# SCH_Tanbre_v2_2026-05-30_4.net
KiCad netlist of a schematic drawn in EasyEDA
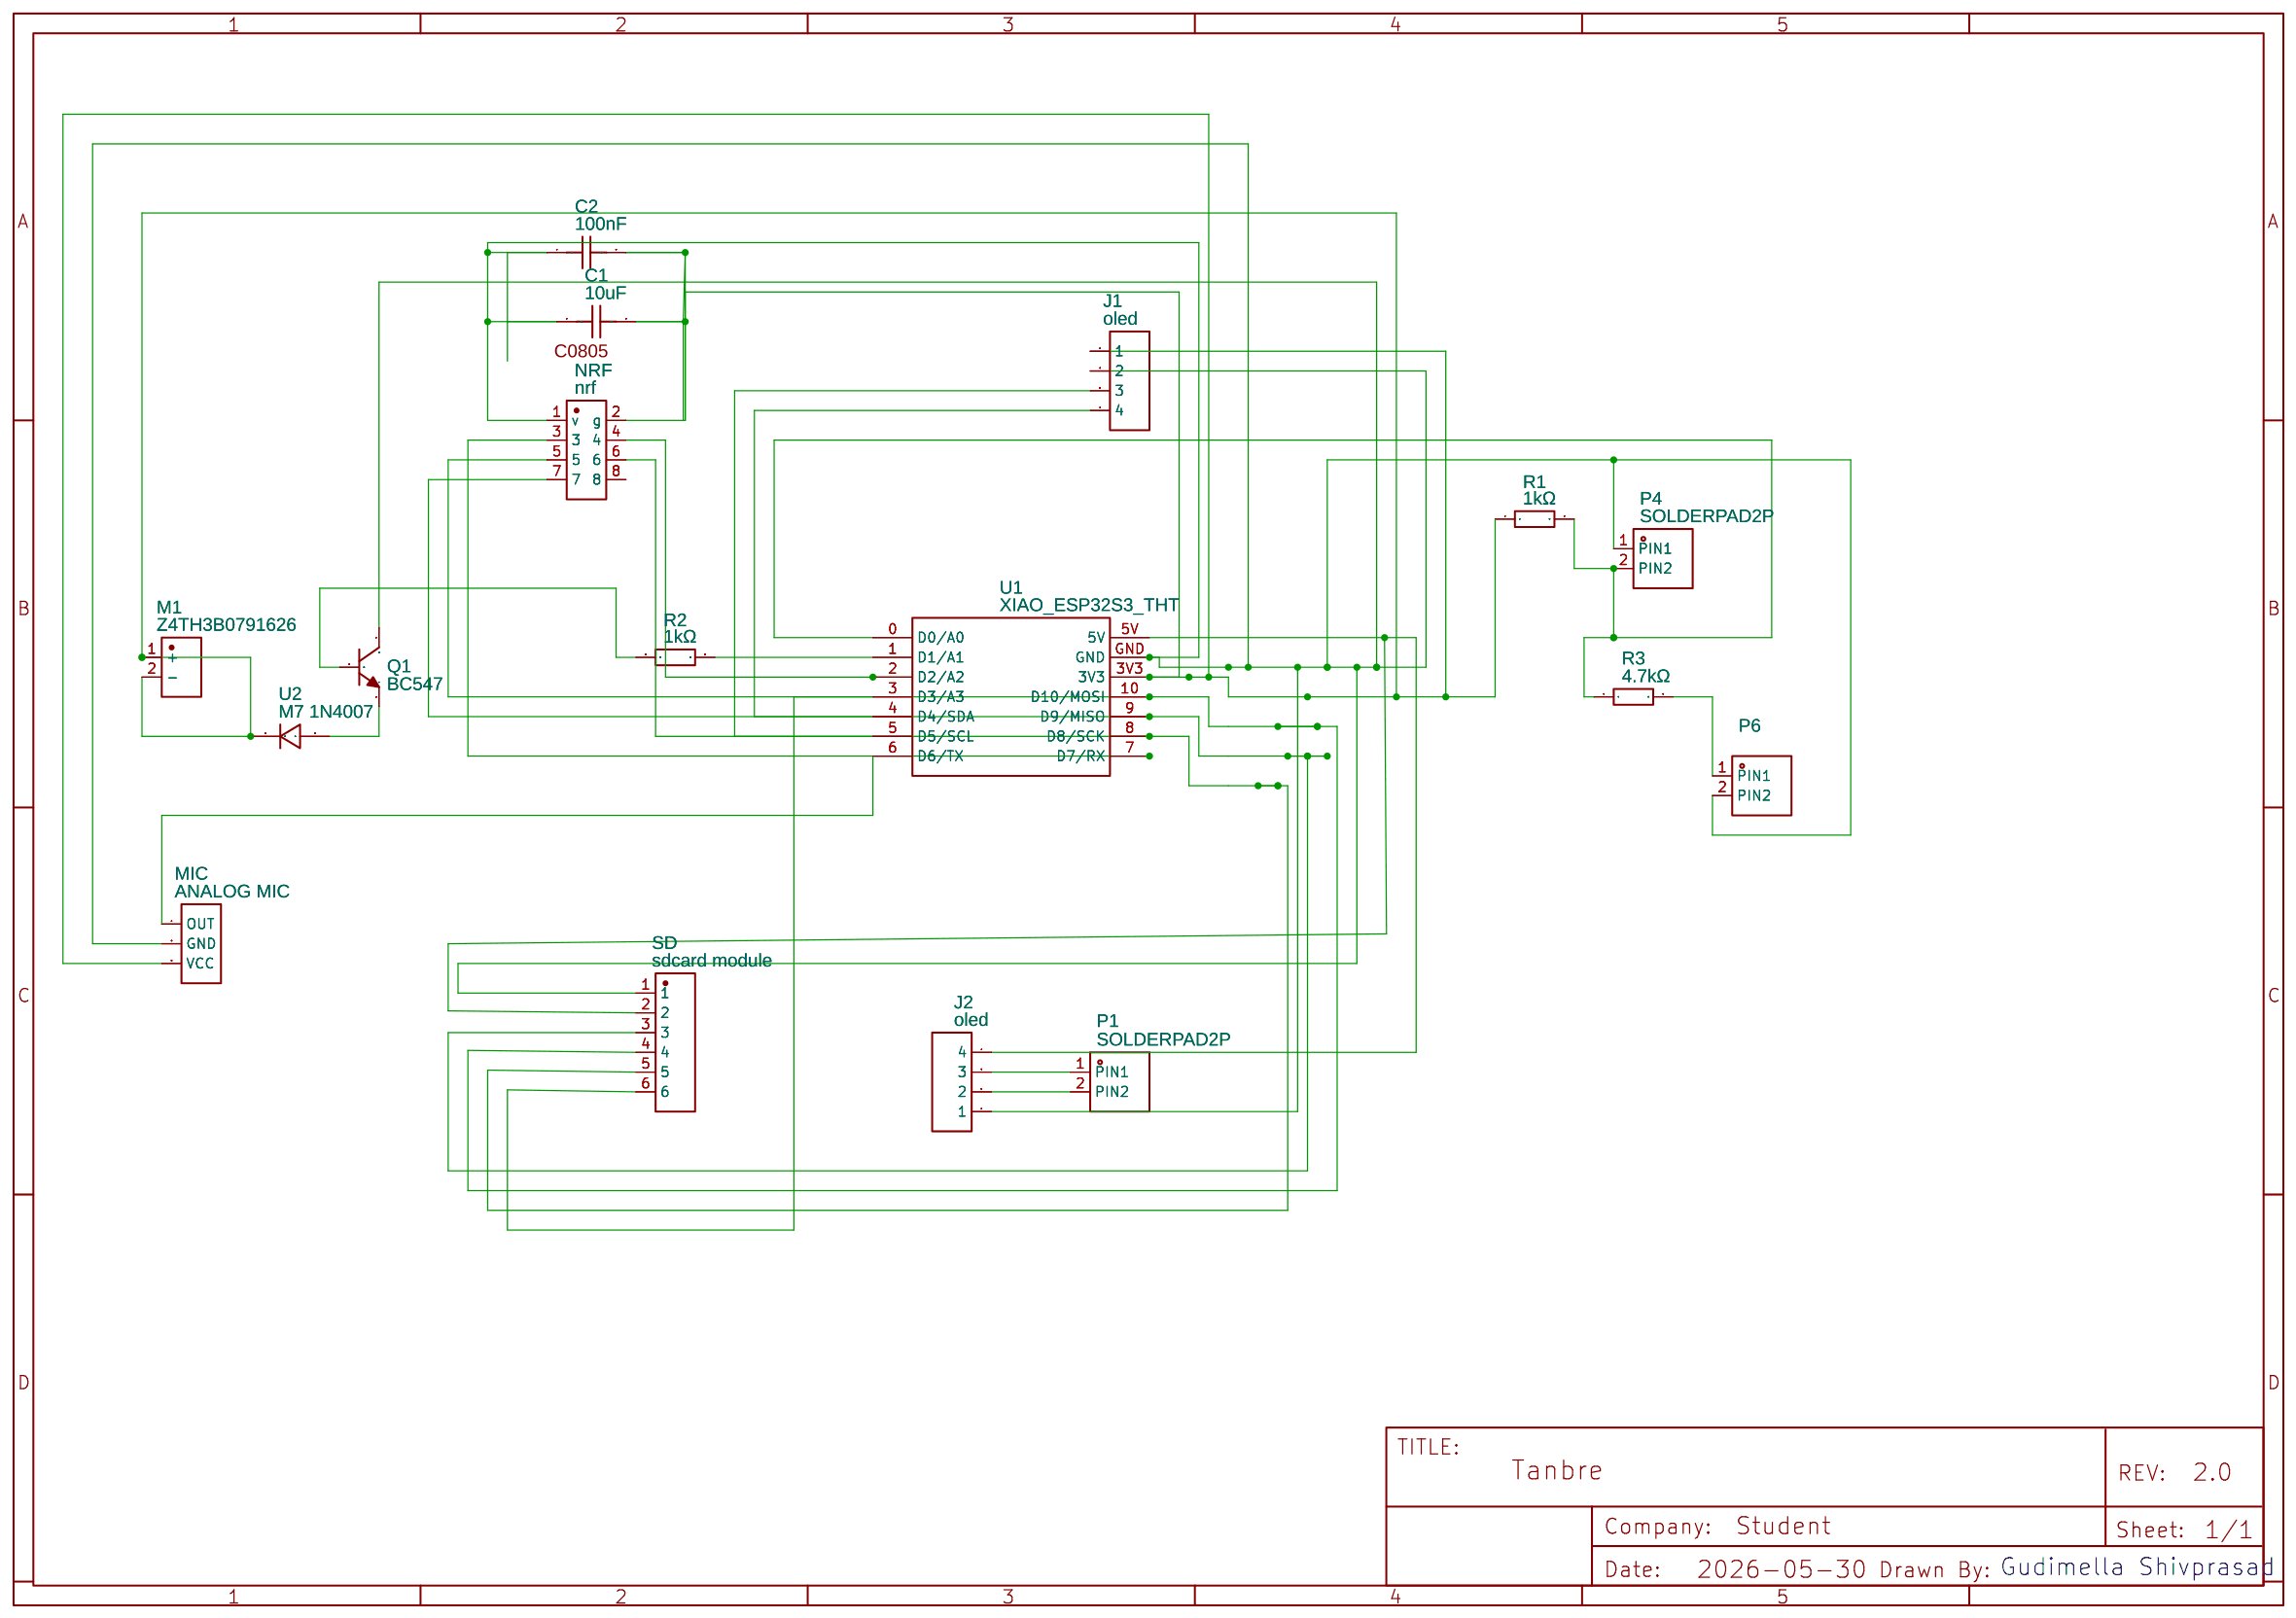
[diagram p0: schematic sheet]

(export (version "E")
  (design (tool "Eeschema 10.0.6"))
  (components
    (comp (ref "C1")
      (value "10uF")
      (fields
        (field (name "Manufacturer Part") "V106K0805X5R250NHP")
        (field (name "Manufacturer") "VIIYONG(微容)")
      )
      (libsource (lib "") (part "V106K0805X5R250NHP"))
    )
    (comp (ref "C2")
      (value "100nF")
      (fields
        (field (name "Manufacturer Part") "VJ0805Y104KXXCW1BC")
        (field (name "Manufacturer") "VISHAY(威世)")
      )
      (libsource (lib "") (part "VJ0805Y104KXXCW1BC"))
    )
    (comp (ref "J1") (value "oled") (libsource (lib "") (part "HDR-M-2.54_1x4_1")))
    (comp (ref "J2") (value "oled") (libsource (lib "") (part "HDR-M-2.54_1x4")))
    (comp (ref "M1")
      (value "Z4TH3B0791626")
      (fields (field (name "Manufacturer") "KOTL(金龙机电)"))
      (libsource (lib "") (part "Z4TH3B0791626"))
    )
    (comp (ref "MIC") (value "ANALOG MIC") (libsource (lib "") (part "HDR-M-2.54_1x3")))
    (comp (ref "NRF")
      (value "nrf")
      (fields (field (name "Manufacturer Part") "2X4 DIP"))
      (libsource (lib "") (part "2X4 DIP"))
    )
    (comp (ref "P1")
      (value "SOLDERPAD2P")
      (fields (field (name "Manufacturer Part") "New SchematicLib"))
      (libsource (lib "") (part "SOLDERPAD2P"))
    )
    (comp (ref "P4")
      (value "SOLDERPAD2P")
      (fields (field (name "Manufacturer Part") "New SchematicLib"))
      (libsource (lib "") (part "SOLDERPAD2P"))
    )
    (comp (ref "P6")
      (value "SOLDERPAD2P")
      (fields (field (name "Manufacturer Part") "New SchematicLib"))
      (libsource (lib "") (part "SOLDERPAD2P"))
    )
    (comp (ref "Q1")
      (value "BC547")
      (fields
        (field (name "Manufacturer Part") "BC547(RANGE:420-800)")
        (field (name "Manufacturer") "CJ(江苏长电/长晶)")
      )
      (libsource (lib "") (part "BC547"))
    )
    (comp (ref "R1")
      (value "1kΩ")
      (fields (field (name "Manufacturer Part") "CR-02JL6----1K") (field (name "Manufacturer") "Viking(光颉)"))
      (libsource (lib "") (part "CR-02JL6----1K"))
    )
    (comp (ref "R2")
      (value "1kΩ")
      (fields (field (name "Manufacturer Part") "CR-02JL6----1K") (field (name "Manufacturer") "Viking(光颉)"))
      (libsource (lib "") (part "CR-02JL6----1K"))
    )
    (comp (ref "R3")
      (value "4.7kΩ")
      (fields (field (name "Manufacturer Part") "RMC12064.7K5%N") (field (name "Manufacturer") "Tyohm(幸亚电阻)"))
      (libsource (lib "") (part "RMC12064.7K5%N"))
    )
    (comp (ref "SD")
      (value "sdcard module")
      (fields
        (field (name "Manufacturer Part") "HC-PM254-5.0H-1x6PZ")
        (field (name "Manufacturer") "HC(虹成电子)")
      )
      (libsource (lib "") (part "HC-PM254-5.0H-1X6PZ"))
    )
    (comp (ref "U1") (value "XIAO_ESP32S3_THT") (libsource (lib "") (part "XIAO_ESP32S3_THT")))
    (comp (ref "U2")
      (value "M7 1N4007")
      (fields (field (name "Manufacturer") "JUXING(钜兴)"))
      (libsource (lib "") (part "M7 1N4007"))
    )
  )
  (nets
    (net (code "1") (name "Net-(J2-Pad4)") (class "Default")
      (node (ref "J2") (pin "4") (pinfunction "4_4") (pintype "unspecified"))
      (node (ref "SD") (pin "2") (pinfunction "2_2") (pintype "unspecified"))
      (node (ref "U1") (pin "5V") (pinfunction "5V_5V") (pintype "unspecified"))
    )
    (net (code "2") (name "Net-(M1-+)") (class "Default")
      (node (ref "C1") (pin "2") (pinfunction "2_2") (pintype "unspecified"))
      (node (ref "C2") (pin "2") (pinfunction "2_2") (pintype "unspecified"))
      (node (ref "J1") (pin "1") (pinfunction "1_1") (pintype "unspecified"))
      (node (ref "M1") (pin "1") (pinfunction "+_1") (pintype "unspecified"))
      (node (ref "M1") (pin "2") (pinfunction "-_2") (pintype "unspecified"))
      (node (ref "MIC") (pin "3") (pinfunction "VCC_3") (pintype "unspecified"))
      (node (ref "NRF") (pin "2") (pinfunction "g_2") (pintype "unspecified"))
      (node (ref "R1") (pin "1") (pinfunction "1_1") (pintype "unspecified"))
      (node (ref "U1") (pin "3V3") (pinfunction "3V3_3V3") (pintype "unspecified"))
      (node (ref "U2") (pin "1") (pinfunction "1_1") (pintype "unspecified"))
    )
    (net (code "3") (name "Net-(MIC-GND)") (class "Default")
      (node (ref "C1") (pin "1") (pinfunction "1_1") (pintype "unspecified"))
      (node (ref "C2") (pin "1") (pinfunction "1_1") (pintype "unspecified"))
      (node (ref "J1") (pin "2") (pinfunction "2_2") (pintype "unspecified"))
      (node (ref "J2") (pin "1") (pinfunction "1_1") (pintype "unspecified"))
      (node (ref "MIC") (pin "2") (pinfunction "GND_2") (pintype "unspecified"))
      (node (ref "NRF") (pin "1") (pinfunction "v_1") (pintype "unspecified"))
      (node (ref "P4") (pin "1") (pinfunction "PIN1_1") (pintype "unspecified"))
      (node (ref "P6") (pin "2") (pinfunction "PIN2_2") (pintype "unspecified"))
      (node (ref "Q1") (pin "1") (pinfunction "C_1") (pintype "unspecified"))
      (node (ref "SD") (pin "1") (pinfunction "1_1") (pintype "unspecified"))
      (node (ref "U1") (pin "GND") (pinfunction "GND_GND") (pintype "unspecified"))
    )
    (net (code "4") (name "Net-(MIC-OUT)") (class "Default")
      (node (ref "MIC") (pin "1") (pinfunction "OUT_1") (pintype "unspecified"))
      (node (ref "U1") (pin "6") (pinfunction "D6/TX_6") (pintype "unspecified"))
    )
    (net (code "5") (name "Net-(P1-PIN1)") (class "Default")
      (node (ref "J2") (pin "3") (pinfunction "3_3") (pintype "unspecified"))
      (node (ref "P1") (pin "1") (pinfunction "PIN1_1") (pintype "unspecified"))
    )
    (net (code "6") (name "Net-(P1-PIN2)") (class "Default")
      (node (ref "J2") (pin "2") (pinfunction "2_2") (pintype "unspecified"))
      (node (ref "P1") (pin "2") (pinfunction "PIN2_2") (pintype "unspecified"))
    )
    (net (code "7") (name "Net-(P4-PIN2)") (class "Default")
      (node (ref "P4") (pin "2") (pinfunction "PIN2_2") (pintype "unspecified"))
      (node (ref "R1") (pin "2") (pinfunction "2_2") (pintype "unspecified"))
      (node (ref "R3") (pin "1") (pinfunction "1_1") (pintype "unspecified"))
      (node (ref "U1") (pin "0") (pinfunction "D0/A0_0") (pintype "unspecified"))
    )
    (net (code "8") (name "Net-(P6-PIN1)") (class "Default")
      (node (ref "P6") (pin "1") (pinfunction "PIN1_1") (pintype "unspecified"))
      (node (ref "R3") (pin "2") (pinfunction "2_2") (pintype "unspecified"))
    )
    (net (code "9") (name "Net-(Q1-B)") (class "Default")
      (node (ref "Q1") (pin "2") (pinfunction "B_2") (pintype "unspecified"))
      (node (ref "R2") (pin "1") (pinfunction "1_1") (pintype "unspecified"))
    )
    (net (code "10") (name "Net-(Q1-E)") (class "Default")
      (node (ref "Q1") (pin "3") (pinfunction "E_3") (pintype "unspecified"))
      (node (ref "U2") (pin "2") (pinfunction "2_2") (pintype "unspecified"))
    )
    (net (code "11") (name "Net-(U1-D1{slash}A1)") (class "Default")
      (node (ref "R2") (pin "2") (pinfunction "2_2") (pintype "unspecified"))
      (node (ref "U1") (pin "1") (pinfunction "D1/A1_1") (pintype "unspecified"))
    )
    (net (code "12") (name "Net-(U1-D2{slash}A2)") (class "Default")
      (node (ref "NRF") (pin "4") (pinfunction "4_4") (pintype "unspecified"))
      (node (ref "U1") (pin "2") (pinfunction "D2/A2_2") (pintype "unspecified"))
    )
    (net (code "13") (name "Net-(U1-D3{slash}A3)") (class "Default")
      (node (ref "SD") (pin "6") (pinfunction "6_6") (pintype "unspecified"))
      (node (ref "U1") (pin "3") (pinfunction "D3/A3_3") (pintype "unspecified"))
    )
    (net (code "14") (name "Net-(U1-D4{slash}SDA)") (class "Default")
      (node (ref "J1") (pin "4") (pinfunction "4_4") (pintype "unspecified"))
      (node (ref "U1") (pin "4") (pinfunction "D4/SDA_4") (pintype "unspecified"))
    )
    (net (code "15") (name "Net-(U1-D5{slash}SCL)") (class "Default")
      (node (ref "J1") (pin "3") (pinfunction "3_3") (pintype "unspecified"))
      (node (ref "U1") (pin "5") (pinfunction "D5/SCL_5") (pintype "unspecified"))
    )
    (net (code "16") (name "Net-(U1-D7{slash}RX)") (class "Default")
      (node (ref "NRF") (pin "3") (pinfunction "3_3") (pintype "unspecified"))
      (node (ref "U1") (pin "7") (pinfunction "D7/RX_7") (pintype "unspecified"))
    )
    (net (code "17") (name "Net-(U1-D8{slash}SCK)") (class "Default")
      (node (ref "NRF") (pin "6") (pinfunction "6_6") (pintype "unspecified"))
      (node (ref "SD") (pin "5") (pinfunction "5_5") (pintype "unspecified"))
      (node (ref "U1") (pin "8") (pinfunction "D8/SCK_8") (pintype "unspecified"))
    )
    (net (code "18") (name "Net-(U1-D9{slash}MISO)") (class "Default")
      (node (ref "NRF") (pin "7") (pinfunction "7_7") (pintype "unspecified"))
      (node (ref "SD") (pin "3") (pinfunction "3_3") (pintype "unspecified"))
      (node (ref "U1") (pin "9") (pinfunction "D9/MISO_9") (pintype "unspecified"))
    )
    (net (code "19") (name "Net-(U1-D10{slash}MOSI)") (class "Default")
      (node (ref "NRF") (pin "5") (pinfunction "5_5") (pintype "unspecified"))
      (node (ref "SD") (pin "4") (pinfunction "4_4") (pintype "unspecified"))
      (node (ref "U1") (pin "10") (pinfunction "D10/MOSI_10") (pintype "unspecified"))
    )
    (net (code "20") (name "unconnected-(NRF-Pad8)") (class "Default")
      (node (ref "NRF") (pin "8") (pinfunction "8_8") (pintype "unspecified"))
    )
  )
)
